# 780-00012-P2_Sch_M2_Focus_Drive.net
KiCad netlist of a schematic drawn in Altium Designer
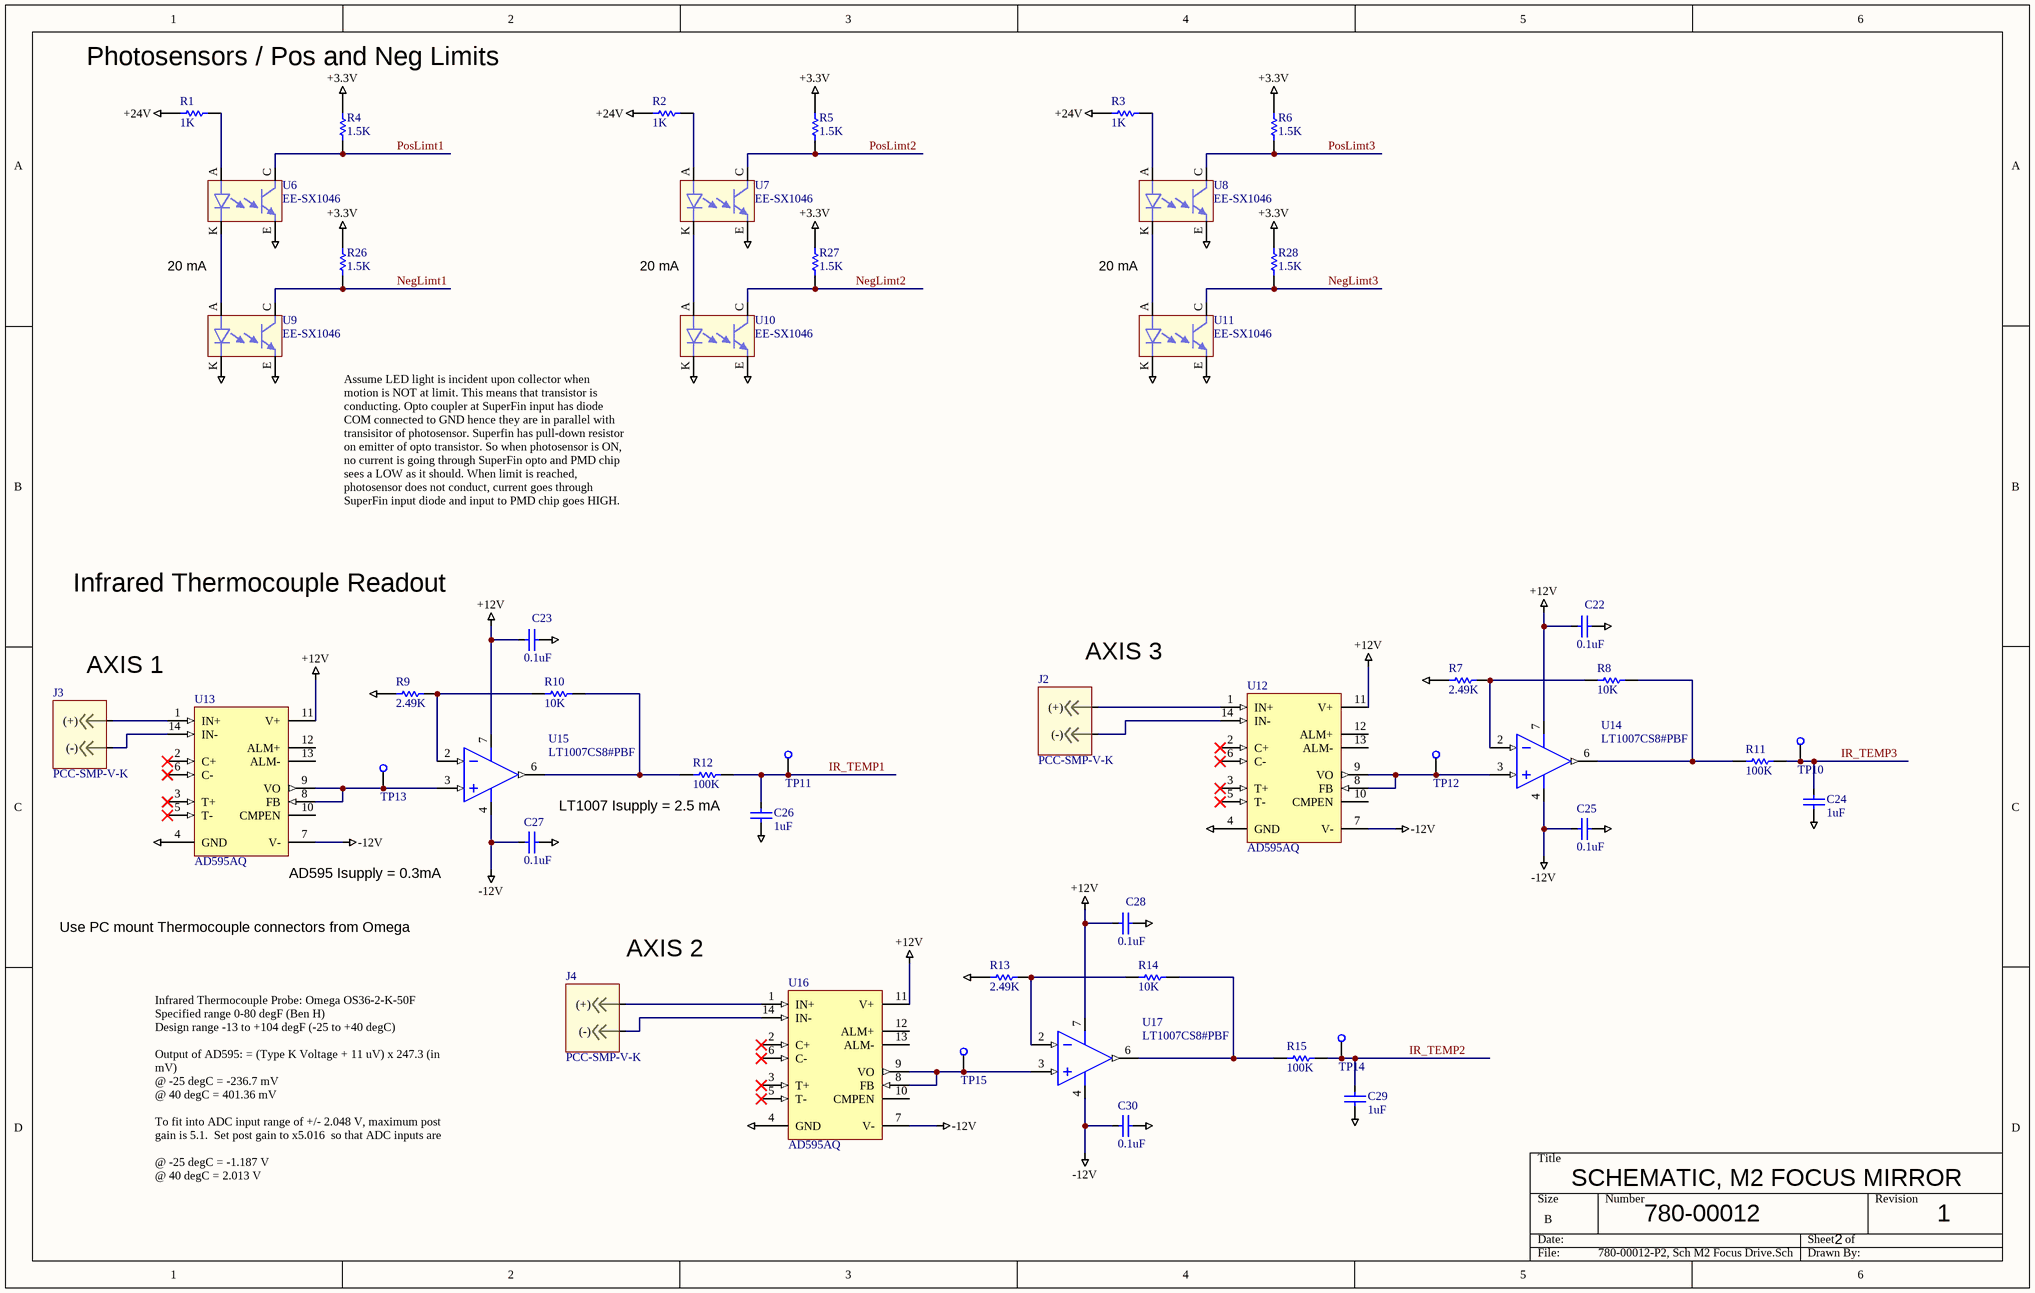
[diagram p0: 780-00012-P2, Sch M2 Focus Drive.SchDoc]

(export (version "E")
  (design (tool "Eeschema 10.0.6"))
  (components
    (comp (ref "C22")
      (value "0.1uF")
      (footprint "SMD_0805")
      (description "Capacitor")
      (fields (field (name "Comment") "Cap SMD"))
      (libsource (lib "Richs Schematic Components") (part "Cap SMD"))
    )
    (comp (ref "C23")
      (value "0.1uF")
      (footprint "SMD_0805")
      (description "Capacitor")
      (fields (field (name "Comment") "Cap SMD"))
      (libsource (lib "Richs Schematic Components") (part "Cap SMD"))
    )
    (comp (ref "C24")
      (value "1uF")
      (footprint "SMD_0805")
      (description "Capacitor")
      (fields (field (name "Comment") "Cap SMD"))
      (libsource (lib "Richs Schematic Components") (part "Cap SMD"))
    )
    (comp (ref "C25")
      (value "0.1uF")
      (footprint "SMD_0805")
      (description "Capacitor")
      (fields (field (name "Comment") "Cap SMD"))
      (libsource (lib "Richs Schematic Components") (part "Cap SMD"))
    )
    (comp (ref "C26")
      (value "1uF")
      (footprint "SMD_0805")
      (description "Capacitor")
      (fields (field (name "Comment") "Cap SMD"))
      (libsource (lib "Richs Schematic Components") (part "Cap SMD"))
    )
    (comp (ref "C27")
      (value "0.1uF")
      (footprint "SMD_0805")
      (description "Capacitor")
      (fields (field (name "Comment") "Cap SMD"))
      (libsource (lib "Richs Schematic Components") (part "Cap SMD"))
    )
    (comp (ref "C28")
      (value "0.1uF")
      (footprint "SMD_0805")
      (description "Capacitor")
      (fields (field (name "Comment") "Cap SMD"))
      (libsource (lib "Richs Schematic Components") (part "Cap SMD"))
    )
    (comp (ref "C29")
      (value "1uF")
      (footprint "SMD_0805")
      (description "Capacitor")
      (fields (field (name "Comment") "Cap SMD"))
      (libsource (lib "Richs Schematic Components") (part "Cap SMD"))
    )
    (comp (ref "C30")
      (value "0.1uF")
      (footprint "SMD_0805")
      (description "Capacitor")
      (fields (field (name "Comment") "Cap SMD"))
      (libsource (lib "Richs Schematic Components") (part "Cap SMD"))
    )
    (comp (ref "J2")
      (value "PCC-SMP-V-K")
      (footprint "THERMOCOUPLE")
      (description "T/C Conn PCB mount vertical")
      (libsource (lib "Richs Schematic Components") (part "Thermocouple Connector"))
    )
    (comp (ref "J3")
      (value "PCC-SMP-V-K")
      (footprint "THERMOCOUPLE")
      (description "T/C Conn PCB mount vertical")
      (libsource (lib "Richs Schematic Components") (part "Thermocouple Connector"))
    )
    (comp (ref "J4")
      (value "PCC-SMP-V-K")
      (footprint "THERMOCOUPLE")
      (description "T/C Conn PCB mount vertical")
      (libsource (lib "Richs Schematic Components") (part "Thermocouple Connector"))
    )
    (comp (ref "R1")
      (value "1K")
      (footprint "SMD_0805")
      (description "Resistor 0805")
      (fields (field (name "MANUFACTURER") "Vishay/Dale") (field (name "Comment") "Res 0805"))
      (libsource (lib "Richs Schematic Components") (part "Res SMD"))
    )
    (comp (ref "R2")
      (value "1K")
      (footprint "SMD_0805")
      (description "Resistor 0805")
      (fields (field (name "MANUFACTURER") "Vishay/Dale") (field (name "Comment") "Res 0805"))
      (libsource (lib "Richs Schematic Components") (part "Res SMD"))
    )
    (comp (ref "R3")
      (value "1K")
      (footprint "SMD_0805")
      (description "Resistor 0805")
      (fields (field (name "MANUFACTURER") "Vishay/Dale") (field (name "Comment") "Res 0805"))
      (libsource (lib "Richs Schematic Components") (part "Res SMD"))
    )
    (comp (ref "R4")
      (value "1.5K")
      (footprint "SMD_0805")
      (description "Resistor 0805")
      (fields (field (name "MANUFACTURER") "Vishay/Dale") (field (name "Comment") "Res 0805"))
      (libsource (lib "Richs Schematic Components") (part "Res SMD"))
    )
    (comp (ref "R5")
      (value "1.5K")
      (footprint "SMD_0805")
      (description "Resistor 0805")
      (fields (field (name "MANUFACTURER") "Vishay/Dale") (field (name "Comment") "Res 0805"))
      (libsource (lib "Richs Schematic Components") (part "Res SMD"))
    )
    (comp (ref "R6")
      (value "1.5K")
      (footprint "SMD_0805")
      (description "Resistor 0805")
      (fields (field (name "MANUFACTURER") "Vishay/Dale") (field (name "Comment") "Res 0805"))
      (libsource (lib "Richs Schematic Components") (part "Res SMD"))
    )
    (comp (ref "R7")
      (value "2.49K")
      (footprint "SMD_0805")
      (description "Resistor 0805")
      (fields (field (name "MANUFACTURER") "Vishay/Dale") (field (name "Comment") "Res 0805"))
      (libsource (lib "Richs Schematic Components") (part "Res SMD"))
    )
    (comp (ref "R8")
      (value "10K")
      (footprint "SMD_0805")
      (description "Resistor 0805")
      (fields (field (name "MANUFACTURER") "Vishay/Dale") (field (name "Comment") "Res 0805"))
      (libsource (lib "Richs Schematic Components") (part "Res SMD"))
    )
    (comp (ref "R9")
      (value "2.49K")
      (footprint "SMD_0805")
      (description "Resistor 0805")
      (fields (field (name "MANUFACTURER") "Vishay/Dale") (field (name "Comment") "Res 0805"))
      (libsource (lib "Richs Schematic Components") (part "Res SMD"))
    )
    (comp (ref "R10")
      (value "10K")
      (footprint "SMD_0805")
      (description "Resistor 0805")
      (fields (field (name "MANUFACTURER") "Vishay/Dale") (field (name "Comment") "Res 0805"))
      (libsource (lib "Richs Schematic Components") (part "Res SMD"))
    )
    (comp (ref "R11")
      (value "100K")
      (footprint "SMD_0805")
      (description "Resistor 0805")
      (fields (field (name "MANUFACTURER") "Vishay/Dale") (field (name "Comment") "Res 0805"))
      (libsource (lib "Richs Schematic Components") (part "Res SMD"))
    )
    (comp (ref "R12")
      (value "100K")
      (footprint "SMD_0805")
      (description "Resistor 0805")
      (fields (field (name "MANUFACTURER") "Vishay/Dale") (field (name "Comment") "Res 0805"))
      (libsource (lib "Richs Schematic Components") (part "Res SMD"))
    )
    (comp (ref "R13")
      (value "2.49K")
      (footprint "SMD_0805")
      (description "Resistor 0805")
      (fields (field (name "MANUFACTURER") "Vishay/Dale") (field (name "Comment") "Res 0805"))
      (libsource (lib "Richs Schematic Components") (part "Res SMD"))
    )
    (comp (ref "R14")
      (value "10K")
      (footprint "SMD_0805")
      (description "Resistor 0805")
      (fields (field (name "MANUFACTURER") "Vishay/Dale") (field (name "Comment") "Res 0805"))
      (libsource (lib "Richs Schematic Components") (part "Res SMD"))
    )
    (comp (ref "R15")
      (value "100K")
      (footprint "SMD_0805")
      (description "Resistor 0805")
      (fields (field (name "MANUFACTURER") "Vishay/Dale") (field (name "Comment") "Res 0805"))
      (libsource (lib "Richs Schematic Components") (part "Res SMD"))
    )
    (comp (ref "R26")
      (value "1.5K")
      (footprint "SMD_0805")
      (description "Resistor 0805")
      (fields (field (name "MANUFACTURER") "Vishay/Dale") (field (name "Comment") "Res 0805"))
      (libsource (lib "Richs Schematic Components") (part "Res SMD"))
    )
    (comp (ref "R27")
      (value "1.5K")
      (footprint "SMD_0805")
      (description "Resistor 0805")
      (fields (field (name "MANUFACTURER") "Vishay/Dale") (field (name "Comment") "Res 0805"))
      (libsource (lib "Richs Schematic Components") (part "Res SMD"))
    )
    (comp (ref "R28")
      (value "1.5K")
      (footprint "SMD_0805")
      (description "Resistor 0805")
      (fields (field (name "MANUFACTURER") "Vishay/Dale") (field (name "Comment") "Res 0805"))
      (libsource (lib "Richs Schematic Components") (part "Res SMD"))
    )
    (comp (ref "TP10")
      (value "Test Point SMD")
      (footprint "SMD_TEST POINT")
      (description "SMD loop test point")
      (libsource (lib "Richs Schematic Components") (part "Test Point SMD"))
    )
    (comp (ref "TP11")
      (value "Test Point SMD")
      (footprint "SMD_TEST POINT")
      (description "SMD loop test point")
      (libsource (lib "Richs Schematic Components") (part "Test Point SMD"))
    )
    (comp (ref "TP12")
      (value "Test Point SMD")
      (footprint "SMD_TEST POINT")
      (description "SMD loop test point")
      (libsource (lib "Richs Schematic Components") (part "Test Point SMD"))
    )
    (comp (ref "TP13")
      (value "Test Point SMD")
      (footprint "SMD_TEST POINT")
      (description "SMD loop test point")
      (libsource (lib "Richs Schematic Components") (part "Test Point SMD"))
    )
    (comp (ref "TP14")
      (value "Test Point SMD")
      (footprint "SMD_TEST POINT")
      (description "SMD loop test point")
      (libsource (lib "Richs Schematic Components") (part "Test Point SMD"))
    )
    (comp (ref "TP15")
      (value "Test Point SMD")
      (footprint "SMD_TEST POINT")
      (description "SMD loop test point")
      (libsource (lib "Richs Schematic Components") (part "Test Point SMD"))
    )
    (comp (ref "U6")
      (value "EE-SX1046")
      (footprint "Photo-sensor")
      (description "Omron EE-SX1046")
      (libsource (lib "Richs Schematic Components") (part "Photo-sensor"))
    )
    (comp (ref "U7")
      (value "EE-SX1046")
      (footprint "Photo-sensor")
      (description "Omron EE-SX1046")
      (libsource (lib "Richs Schematic Components") (part "Photo-sensor"))
    )
    (comp (ref "U8")
      (value "EE-SX1046")
      (footprint "Photo-sensor")
      (description "Omron EE-SX1046")
      (libsource (lib "Richs Schematic Components") (part "Photo-sensor"))
    )
    (comp (ref "U9")
      (value "EE-SX1046")
      (footprint "Photo-sensor")
      (description "Omron EE-SX1046")
      (libsource (lib "Richs Schematic Components") (part "Photo-sensor"))
    )
    (comp (ref "U10")
      (value "EE-SX1046")
      (footprint "Photo-sensor")
      (description "Omron EE-SX1046")
      (libsource (lib "Richs Schematic Components") (part "Photo-sensor"))
    )
    (comp (ref "U11")
      (value "EE-SX1046")
      (footprint "Photo-sensor")
      (description "Omron EE-SX1046")
      (libsource (lib "Richs Schematic Components") (part "Photo-sensor"))
    )
    (comp (ref "U12")
      (value "AD595AQ")
      (footprint "Q-14_A")
      (description "Monolithic Thermocouple Amplifier with Cold Junction Compensation")
      (fields (field (name "MANUFACTURER") "Analog Devices"))
      (libsource (lib "AD Thermocouple Amplifier") (part "AD595AQ"))
    )
    (comp (ref "U13")
      (value "AD595AQ")
      (footprint "Q-14_A")
      (description "Monolithic Thermocouple Amplifier with Cold Junction Compensation")
      (fields (field (name "MANUFACTURER") "Analog Devices"))
      (libsource (lib "AD Thermocouple Amplifier") (part "AD595AQ"))
    )
    (comp (ref "U14")
      (value "LT1007CS8#PBF")
      (footprint "S8_M")
      (description "Low Noise BJT input opamp")
      (fields (field (name "MANUFACTURER") "Linear Tech"))
      (libsource (lib "Richs Schematic Components") (part "LT1007CS8#PBF"))
    )
    (comp (ref "U15")
      (value "LT1007CS8#PBF")
      (footprint "S8_M")
      (description "Low Noise BJT input opamp")
      (fields (field (name "MANUFACTURER") "Linear Tech"))
      (libsource (lib "Richs Schematic Components") (part "LT1007CS8#PBF"))
    )
    (comp (ref "U16")
      (value "AD595AQ")
      (footprint "Q-14_A")
      (description "Monolithic Thermocouple Amplifier with Cold Junction Compensation")
      (fields (field (name "MANUFACTURER") "Analog Devices"))
      (libsource (lib "AD Thermocouple Amplifier") (part "AD595AQ"))
    )
    (comp (ref "U17")
      (value "LT1007CS8#PBF")
      (footprint "S8_M")
      (description "Low Noise BJT input opamp")
      (fields (field (name "MANUFACTURER") "Linear Tech"))
      (libsource (lib "Richs Schematic Components") (part "LT1007CS8#PBF"))
    )
  )
  (nets
    (net (code "1") (name "+3.3V") (class "Default")
      (node (ref "R26") (pin "2") (pinfunction "2_2") (pintype "passive"))
      (node (ref "R27") (pin "2") (pinfunction "2_2") (pintype "passive"))
      (node (ref "R28") (pin "2") (pinfunction "2_2") (pintype "passive"))
      (node (ref "R4") (pin "2") (pinfunction "2_2") (pintype "passive"))
      (node (ref "R5") (pin "2") (pinfunction "2_2") (pintype "passive"))
      (node (ref "R6") (pin "2") (pinfunction "2_2") (pintype "passive"))
    )
    (net (code "2") (name "+12V") (class "Default")
      (node (ref "C22") (pin "2") (pinfunction "2_2") (pintype "passive"))
      (node (ref "C23") (pin "2") (pinfunction "2_2") (pintype "passive"))
      (node (ref "C28") (pin "2") (pinfunction "2_2") (pintype "passive"))
      (node (ref "U12") (pin "11") (pinfunction "V+_11") (pintype "power_in"))
      (node (ref "U13") (pin "11") (pinfunction "V+_11") (pintype "power_in"))
      (node (ref "U14") (pin "7") (pinfunction "V+_7") (pintype "power_in"))
      (node (ref "U15") (pin "7") (pinfunction "V+_7") (pintype "power_in"))
      (node (ref "U16") (pin "11") (pinfunction "V+_11") (pintype "power_in"))
      (node (ref "U17") (pin "7") (pinfunction "V+_7") (pintype "power_in"))
    )
    (net (code "3") (name "+24V") (class "Default")
      (node (ref "R1") (pin "2") (pinfunction "2_2") (pintype "passive"))
      (node (ref "R2") (pin "2") (pinfunction "2_2") (pintype "passive"))
      (node (ref "R3") (pin "2") (pinfunction "2_2") (pintype "passive"))
    )
    (net (code "4") (name "-12V") (class "Default")
      (node (ref "C25") (pin "2") (pinfunction "2_2") (pintype "passive"))
      (node (ref "C27") (pin "2") (pinfunction "2_2") (pintype "passive"))
      (node (ref "C30") (pin "2") (pinfunction "2_2") (pintype "passive"))
      (node (ref "U12") (pin "7") (pinfunction "V-_7") (pintype "power_in"))
      (node (ref "U13") (pin "7") (pinfunction "V-_7") (pintype "power_in"))
      (node (ref "U14") (pin "4") (pinfunction "V-_4") (pintype "power_in"))
      (node (ref "U15") (pin "4") (pinfunction "V-_4") (pintype "power_in"))
      (node (ref "U16") (pin "7") (pinfunction "V-_7") (pintype "power_in"))
      (node (ref "U17") (pin "4") (pinfunction "V-_4") (pintype "power_in"))
    )
    (net (code "5") (name "/IR_TEMP1") (class "Default")
      (node (ref "C26") (pin "2") (pinfunction "2_2") (pintype "passive"))
      (node (ref "R12") (pin "2") (pinfunction "2_2") (pintype "passive"))
      (node (ref "TP11") (pin "1") (pinfunction "TP_1") (pintype "passive"))
    )
    (net (code "6") (name "/IR_TEMP2") (class "Default")
      (node (ref "C29") (pin "2") (pinfunction "2_2") (pintype "passive"))
      (node (ref "R15") (pin "2") (pinfunction "2_2") (pintype "passive"))
      (node (ref "TP14") (pin "1") (pinfunction "TP_1") (pintype "passive"))
    )
    (net (code "7") (name "/IR_TEMP3") (class "Default")
      (node (ref "C24") (pin "2") (pinfunction "2_2") (pintype "passive"))
      (node (ref "R11") (pin "2") (pinfunction "2_2") (pintype "passive"))
      (node (ref "TP10") (pin "1") (pinfunction "TP_1") (pintype "passive"))
    )
    (net (code "8") (name "/NegLimt1") (class "Default")
      (node (ref "R26") (pin "1") (pinfunction "1_1") (pintype "passive"))
      (node (ref "U9") (pin "C") (pinfunction "collector_C") (pintype "passive"))
    )
    (net (code "9") (name "/NegLimt2") (class "Default")
      (node (ref "R27") (pin "1") (pinfunction "1_1") (pintype "passive"))
      (node (ref "U10") (pin "C") (pinfunction "collector_C") (pintype "passive"))
    )
    (net (code "10") (name "/NegLimt3") (class "Default")
      (node (ref "R28") (pin "1") (pinfunction "1_1") (pintype "passive"))
      (node (ref "U11") (pin "C") (pinfunction "collector_C") (pintype "passive"))
    )
    (net (code "11") (name "/PosLimt1") (class "Default")
      (node (ref "R4") (pin "1") (pinfunction "1_1") (pintype "passive"))
      (node (ref "U6") (pin "C") (pinfunction "collector_C") (pintype "passive"))
    )
    (net (code "12") (name "/PosLimt2") (class "Default")
      (node (ref "R5") (pin "1") (pinfunction "1_1") (pintype "passive"))
      (node (ref "U7") (pin "C") (pinfunction "collector_C") (pintype "passive"))
    )
    (net (code "13") (name "/PosLimt3") (class "Default")
      (node (ref "R6") (pin "1") (pinfunction "1_1") (pintype "passive"))
      (node (ref "U8") (pin "C") (pinfunction "collector_C") (pintype "passive"))
    )
    (net (code "14") (name "GND") (class "Default")
      (node (ref "C22") (pin "1") (pinfunction "1_1") (pintype "passive"))
      (node (ref "C23") (pin "1") (pinfunction "1_1") (pintype "passive"))
      (node (ref "C24") (pin "1") (pinfunction "1_1") (pintype "passive"))
      (node (ref "C25") (pin "1") (pinfunction "1_1") (pintype "passive"))
      (node (ref "C26") (pin "1") (pinfunction "1_1") (pintype "passive"))
      (node (ref "C27") (pin "1") (pinfunction "1_1") (pintype "passive"))
      (node (ref "C28") (pin "1") (pinfunction "1_1") (pintype "passive"))
      (node (ref "C29") (pin "1") (pinfunction "1_1") (pintype "passive"))
      (node (ref "C30") (pin "1") (pinfunction "1_1") (pintype "passive"))
      (node (ref "R13") (pin "1") (pinfunction "1_1") (pintype "passive"))
      (node (ref "R7") (pin "1") (pinfunction "1_1") (pintype "passive"))
      (node (ref "R9") (pin "1") (pinfunction "1_1") (pintype "passive"))
      (node (ref "U10") (pin "E") (pinfunction "emitter_E") (pintype "passive"))
      (node (ref "U10") (pin "K") (pinfunction "cathode_K") (pintype "passive"))
      (node (ref "U11") (pin "E") (pinfunction "emitter_E") (pintype "passive"))
      (node (ref "U11") (pin "K") (pinfunction "cathode_K") (pintype "passive"))
      (node (ref "U12") (pin "4") (pinfunction "GND_4") (pintype "power_in"))
      (node (ref "U13") (pin "4") (pinfunction "GND_4") (pintype "power_in"))
      (node (ref "U16") (pin "4") (pinfunction "GND_4") (pintype "power_in"))
      (node (ref "U6") (pin "E") (pinfunction "emitter_E") (pintype "passive"))
      (node (ref "U7") (pin "E") (pinfunction "emitter_E") (pintype "passive"))
      (node (ref "U8") (pin "E") (pinfunction "emitter_E") (pintype "passive"))
      (node (ref "U9") (pin "E") (pinfunction "emitter_E") (pintype "passive"))
      (node (ref "U9") (pin "K") (pinfunction "cathode_K") (pintype "passive"))
    )
    (net (code "15") (name "Net-(J2-(+))") (class "Default")
      (node (ref "J2") (pin "1") (pinfunction "(+)_1") (pintype "passive"))
      (node (ref "U12") (pin "1") (pinfunction "IN+_1") (pintype "input"))
    )
    (net (code "16") (name "Net-(J2-(-))") (class "Default")
      (node (ref "J2") (pin "2") (pinfunction "(-)_2") (pintype "passive"))
      (node (ref "U12") (pin "14") (pinfunction "IN-_14") (pintype "input"))
    )
    (net (code "17") (name "Net-(J3-(+))") (class "Default")
      (node (ref "J3") (pin "1") (pinfunction "(+)_1") (pintype "passive"))
      (node (ref "U13") (pin "1") (pinfunction "IN+_1") (pintype "input"))
    )
    (net (code "18") (name "Net-(J3-(-))") (class "Default")
      (node (ref "J3") (pin "2") (pinfunction "(-)_2") (pintype "passive"))
      (node (ref "U13") (pin "14") (pinfunction "IN-_14") (pintype "input"))
    )
    (net (code "19") (name "Net-(J4-(+))") (class "Default")
      (node (ref "J4") (pin "1") (pinfunction "(+)_1") (pintype "passive"))
      (node (ref "U16") (pin "1") (pinfunction "IN+_1") (pintype "input"))
    )
    (net (code "20") (name "Net-(J4-(-))") (class "Default")
      (node (ref "J4") (pin "2") (pinfunction "(-)_2") (pintype "passive"))
      (node (ref "U16") (pin "14") (pinfunction "IN-_14") (pintype "input"))
    )
    (net (code "21") (name "Net-(TP12-TP)") (class "Default")
      (node (ref "TP12") (pin "1") (pinfunction "TP_1") (pintype "passive"))
      (node (ref "U12") (pin "8") (pinfunction "FB_8") (pintype "input"))
      (node (ref "U12") (pin "9") (pinfunction "VO_9") (pintype "output"))
      (node (ref "U14") (pin "3") (pinfunction "IN+_3") (pintype "input"))
    )
    (net (code "22") (name "Net-(TP13-TP)") (class "Default")
      (node (ref "TP13") (pin "1") (pinfunction "TP_1") (pintype "passive"))
      (node (ref "U13") (pin "8") (pinfunction "FB_8") (pintype "input"))
      (node (ref "U13") (pin "9") (pinfunction "VO_9") (pintype "output"))
      (node (ref "U15") (pin "3") (pinfunction "IN+_3") (pintype "input"))
    )
    (net (code "23") (name "Net-(TP15-TP)") (class "Default")
      (node (ref "TP15") (pin "1") (pinfunction "TP_1") (pintype "passive"))
      (node (ref "U16") (pin "8") (pinfunction "FB_8") (pintype "input"))
      (node (ref "U16") (pin "9") (pinfunction "VO_9") (pintype "output"))
      (node (ref "U17") (pin "3") (pinfunction "IN+_3") (pintype "input"))
    )
    (net (code "24") (name "Net-(U6-anode)") (class "Default")
      (node (ref "R1") (pin "1") (pinfunction "1_1") (pintype "passive"))
      (node (ref "U6") (pin "A") (pinfunction "anode_A") (pintype "passive"))
    )
    (net (code "25") (name "Net-(U6-cathode)") (class "Default")
      (node (ref "U6") (pin "K") (pinfunction "cathode_K") (pintype "passive"))
      (node (ref "U9") (pin "A") (pinfunction "anode_A") (pintype "passive"))
    )
    (net (code "26") (name "Net-(U7-anode)") (class "Default")
      (node (ref "R2") (pin "1") (pinfunction "1_1") (pintype "passive"))
      (node (ref "U7") (pin "A") (pinfunction "anode_A") (pintype "passive"))
    )
    (net (code "27") (name "Net-(U8-anode)") (class "Default")
      (node (ref "R3") (pin "1") (pinfunction "1_1") (pintype "passive"))
      (node (ref "U8") (pin "A") (pinfunction "anode_A") (pintype "passive"))
    )
    (net (code "28") (name "Net-(U10-anode)") (class "Default")
      (node (ref "U10") (pin "A") (pinfunction "anode_A") (pintype "passive"))
      (node (ref "U7") (pin "K") (pinfunction "cathode_K") (pintype "passive"))
    )
    (net (code "29") (name "Net-(U11-anode)") (class "Default")
      (node (ref "U11") (pin "A") (pinfunction "anode_A") (pintype "passive"))
      (node (ref "U8") (pin "K") (pinfunction "cathode_K") (pintype "passive"))
    )
    (net (code "30") (name "Net-(U14-IN-)") (class "Default")
      (node (ref "R7") (pin "2") (pinfunction "2_2") (pintype "passive"))
      (node (ref "R8") (pin "1") (pinfunction "1_1") (pintype "passive"))
      (node (ref "U14") (pin "2") (pinfunction "IN-_2") (pintype "input"))
    )
    (net (code "31") (name "Net-(U14-OUT)") (class "Default")
      (node (ref "R11") (pin "1") (pinfunction "1_1") (pintype "passive"))
      (node (ref "R8") (pin "2") (pinfunction "2_2") (pintype "passive"))
      (node (ref "U14") (pin "6") (pinfunction "OUT_6") (pintype "output"))
    )
    (net (code "32") (name "Net-(U15-IN-)") (class "Default")
      (node (ref "R10") (pin "1") (pinfunction "1_1") (pintype "passive"))
      (node (ref "R9") (pin "2") (pinfunction "2_2") (pintype "passive"))
      (node (ref "U15") (pin "2") (pinfunction "IN-_2") (pintype "input"))
    )
    (net (code "33") (name "Net-(U15-OUT)") (class "Default")
      (node (ref "R10") (pin "2") (pinfunction "2_2") (pintype "passive"))
      (node (ref "R12") (pin "1") (pinfunction "1_1") (pintype "passive"))
      (node (ref "U15") (pin "6") (pinfunction "OUT_6") (pintype "output"))
    )
    (net (code "34") (name "Net-(U17-IN-)") (class "Default")
      (node (ref "R13") (pin "2") (pinfunction "2_2") (pintype "passive"))
      (node (ref "R14") (pin "1") (pinfunction "1_1") (pintype "passive"))
      (node (ref "U17") (pin "2") (pinfunction "IN-_2") (pintype "input"))
    )
    (net (code "35") (name "Net-(U17-OUT)") (class "Default")
      (node (ref "R14") (pin "2") (pinfunction "2_2") (pintype "passive"))
      (node (ref "R15") (pin "1") (pinfunction "1_1") (pintype "passive"))
      (node (ref "U17") (pin "6") (pinfunction "OUT_6") (pintype "output"))
    )
    (net (code "36") (name "unconnected-(U12-ALM+-Pad12)") (class "Default")
      (node (ref "U12") (pin "12") (pinfunction "ALM+_12") (pintype "passive"))
    )
    (net (code "37") (name "unconnected-(U12-ALM--Pad13)") (class "Default")
      (node (ref "U12") (pin "13") (pinfunction "ALM-_13") (pintype "passive"))
    )
    (net (code "38") (name "unconnected-(U12-C+-Pad2)") (class "Default")
      (node (ref "U12") (pin "2") (pinfunction "C+_2") (pintype "input+no_connect"))
    )
    (net (code "39") (name "unconnected-(U12-C--Pad6)") (class "Default")
      (node (ref "U12") (pin "6") (pinfunction "C-_6") (pintype "input+no_connect"))
    )
    (net (code "40") (name "unconnected-(U12-CMPEN-Pad10)") (class "Default")
      (node (ref "U12") (pin "10") (pinfunction "CMPEN_10") (pintype "passive"))
    )
    (net (code "41") (name "unconnected-(U12-T+-Pad3)") (class "Default")
      (node (ref "U12") (pin "3") (pinfunction "T+_3") (pintype "input+no_connect"))
    )
    (net (code "42") (name "unconnected-(U12-T--Pad5)") (class "Default")
      (node (ref "U12") (pin "5") (pinfunction "T-_5") (pintype "input+no_connect"))
    )
    (net (code "43") (name "unconnected-(U13-ALM+-Pad12)") (class "Default")
      (node (ref "U13") (pin "12") (pinfunction "ALM+_12") (pintype "passive"))
    )
    (net (code "44") (name "unconnected-(U13-ALM--Pad13)") (class "Default")
      (node (ref "U13") (pin "13") (pinfunction "ALM-_13") (pintype "passive"))
    )
    (net (code "45") (name "unconnected-(U13-C+-Pad2)") (class "Default")
      (node (ref "U13") (pin "2") (pinfunction "C+_2") (pintype "input+no_connect"))
    )
    (net (code "46") (name "unconnected-(U13-C--Pad6)") (class "Default")
      (node (ref "U13") (pin "6") (pinfunction "C-_6") (pintype "input+no_connect"))
    )
    (net (code "47") (name "unconnected-(U13-CMPEN-Pad10)") (class "Default")
      (node (ref "U13") (pin "10") (pinfunction "CMPEN_10") (pintype "passive"))
    )
    (net (code "48") (name "unconnected-(U13-T+-Pad3)") (class "Default")
      (node (ref "U13") (pin "3") (pinfunction "T+_3") (pintype "input+no_connect"))
    )
    (net (code "49") (name "unconnected-(U13-T--Pad5)") (class "Default")
      (node (ref "U13") (pin "5") (pinfunction "T-_5") (pintype "input+no_connect"))
    )
    (net (code "50") (name "unconnected-(U14-NC-Pad5)") (class "Default")
      (node (ref "U14") (pin "5") (pinfunction "NC_5") (pintype "passive"))
    )
    (net (code "51") (name "unconnected-(U14-VOSTRIM-Pad1)") (class "Default")
      (node (ref "U14") (pin "1") (pinfunction "VOSTRIM_1") (pintype "passive"))
    )
    (net (code "52") (name "unconnected-(U14-VOSTRIM-Pad8)") (class "Default")
      (node (ref "U14") (pin "8") (pinfunction "VOSTRIM_8") (pintype "passive"))
    )
    (net (code "53") (name "unconnected-(U15-NC-Pad5)") (class "Default")
      (node (ref "U15") (pin "5") (pinfunction "NC_5") (pintype "passive"))
    )
    (net (code "54") (name "unconnected-(U15-VOSTRIM-Pad1)") (class "Default")
      (node (ref "U15") (pin "1") (pinfunction "VOSTRIM_1") (pintype "passive"))
    )
    (net (code "55") (name "unconnected-(U15-VOSTRIM-Pad8)") (class "Default")
      (node (ref "U15") (pin "8") (pinfunction "VOSTRIM_8") (pintype "passive"))
    )
    (net (code "56") (name "unconnected-(U16-ALM+-Pad12)") (class "Default")
      (node (ref "U16") (pin "12") (pinfunction "ALM+_12") (pintype "passive"))
    )
    (net (code "57") (name "unconnected-(U16-ALM--Pad13)") (class "Default")
      (node (ref "U16") (pin "13") (pinfunction "ALM-_13") (pintype "passive"))
    )
    (net (code "58") (name "unconnected-(U16-C+-Pad2)") (class "Default")
      (node (ref "U16") (pin "2") (pinfunction "C+_2") (pintype "input+no_connect"))
    )
    (net (code "59") (name "unconnected-(U16-C--Pad6)") (class "Default")
      (node (ref "U16") (pin "6") (pinfunction "C-_6") (pintype "input+no_connect"))
    )
    (net (code "60") (name "unconnected-(U16-CMPEN-Pad10)") (class "Default")
      (node (ref "U16") (pin "10") (pinfunction "CMPEN_10") (pintype "passive"))
    )
    (net (code "61") (name "unconnected-(U16-T+-Pad3)") (class "Default")
      (node (ref "U16") (pin "3") (pinfunction "T+_3") (pintype "input+no_connect"))
    )
    (net (code "62") (name "unconnected-(U16-T--Pad5)") (class "Default")
      (node (ref "U16") (pin "5") (pinfunction "T-_5") (pintype "input+no_connect"))
    )
    (net (code "63") (name "unconnected-(U17-NC-Pad5)") (class "Default")
      (node (ref "U17") (pin "5") (pinfunction "NC_5") (pintype "passive"))
    )
    (net (code "64") (name "unconnected-(U17-VOSTRIM-Pad1)") (class "Default")
      (node (ref "U17") (pin "1") (pinfunction "VOSTRIM_1") (pintype "passive"))
    )
    (net (code "65") (name "unconnected-(U17-VOSTRIM-Pad8)") (class "Default")
      (node (ref "U17") (pin "8") (pinfunction "VOSTRIM_8") (pintype "passive"))
    )
  )
)
